# hv_psu_v100_CON.net
KiCad netlist of a schematic drawn in Altium Designer
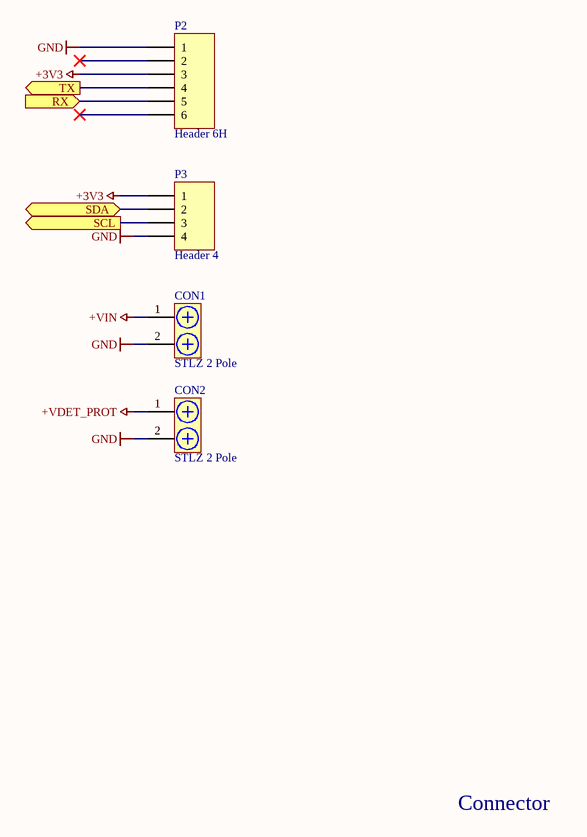
[diagram p0: hv_psu_v100_CON.SchDoc]

(export (version "E")
  (design (tool "Eeschema 10.0.6"))
  (components
    (comp (ref "CON1")
      (value "STLZ 2 Pole")
      (footprint "CON_STLZ_950WV2 + AKZ 950/2")
      (libsource (lib "connector") (part "STLZ 2 Pole"))
    )
    (comp (ref "CON2")
      (value "STLZ 2 Pole")
      (footprint "CON_STLZ_950WV2 + AKZ 950/2")
      (libsource (lib "connector") (part "STLZ 2 Pole"))
    )
    (comp (ref "P2")
      (value "Header 6H")
      (footprint "HDR1X6H")
      (description "Header, 6-Pin, Right Angle")
      (fields (field (name "PUBLISHER") "Altium Limited"))
      (libsource (lib "Miscellaneous Connectors") (part "Header 6H"))
    )
    (comp (ref "P3")
      (value "Header 4")
      (footprint "HDR1X4")
      (description "Header, 4-Pin")
      (fields (field (name "PUBLISHER") "Altium Limited"))
      (libsource (lib "Miscellaneous Connectors") (part "Header 4"))
    )
  )
  (nets
    (net (code "1") (name "+3V3") (class "Default")
      (node (ref "P2") (pin "3") (pinfunction "3_3") (pintype "passive"))
      (node (ref "P3") (pin "1") (pinfunction "1_1") (pintype "passive"))
    )
    (net (code "2") (name "+VDET_PROT") (class "Default")
      (node (ref "CON2") (pin "1") (pinfunction "1_1") (pintype "passive"))
    )
    (net (code "3") (name "+VIN") (class "Default")
      (node (ref "CON1") (pin "1") (pinfunction "1_1") (pintype "passive"))
    )
    (net (code "4") (name "/RX") (class "Default")
      (node (ref "P2") (pin "5") (pinfunction "5_5") (pintype "passive"))
    )
    (net (code "5") (name "/SCL") (class "Default")
      (node (ref "P3") (pin "3") (pinfunction "3_3") (pintype "passive"))
    )
    (net (code "6") (name "/SDA") (class "Default")
      (node (ref "P3") (pin "2") (pinfunction "2_2") (pintype "passive"))
    )
    (net (code "7") (name "/TX") (class "Default")
      (node (ref "P2") (pin "4") (pinfunction "4_4") (pintype "passive"))
    )
    (net (code "8") (name "GND") (class "Default")
      (node (ref "CON1") (pin "2") (pinfunction "2_2") (pintype "passive"))
      (node (ref "CON2") (pin "2") (pinfunction "2_2") (pintype "passive"))
      (node (ref "P2") (pin "1") (pinfunction "1_1") (pintype "passive"))
      (node (ref "P3") (pin "4") (pinfunction "4_4") (pintype "passive"))
    )
    (net (code "9") (name "unconnected-(P2-Pad2)") (class "Default")
      (node (ref "P2") (pin "2") (pinfunction "2_2") (pintype "passive+no_connect"))
    )
    (net (code "10") (name "unconnected-(P2-Pad6)") (class "Default")
      (node (ref "P2") (pin "6") (pinfunction "6_6") (pintype "passive+no_connect"))
    )
  )
)
